# combined.net
KiCad netlist of a schematic drawn in EAGLE
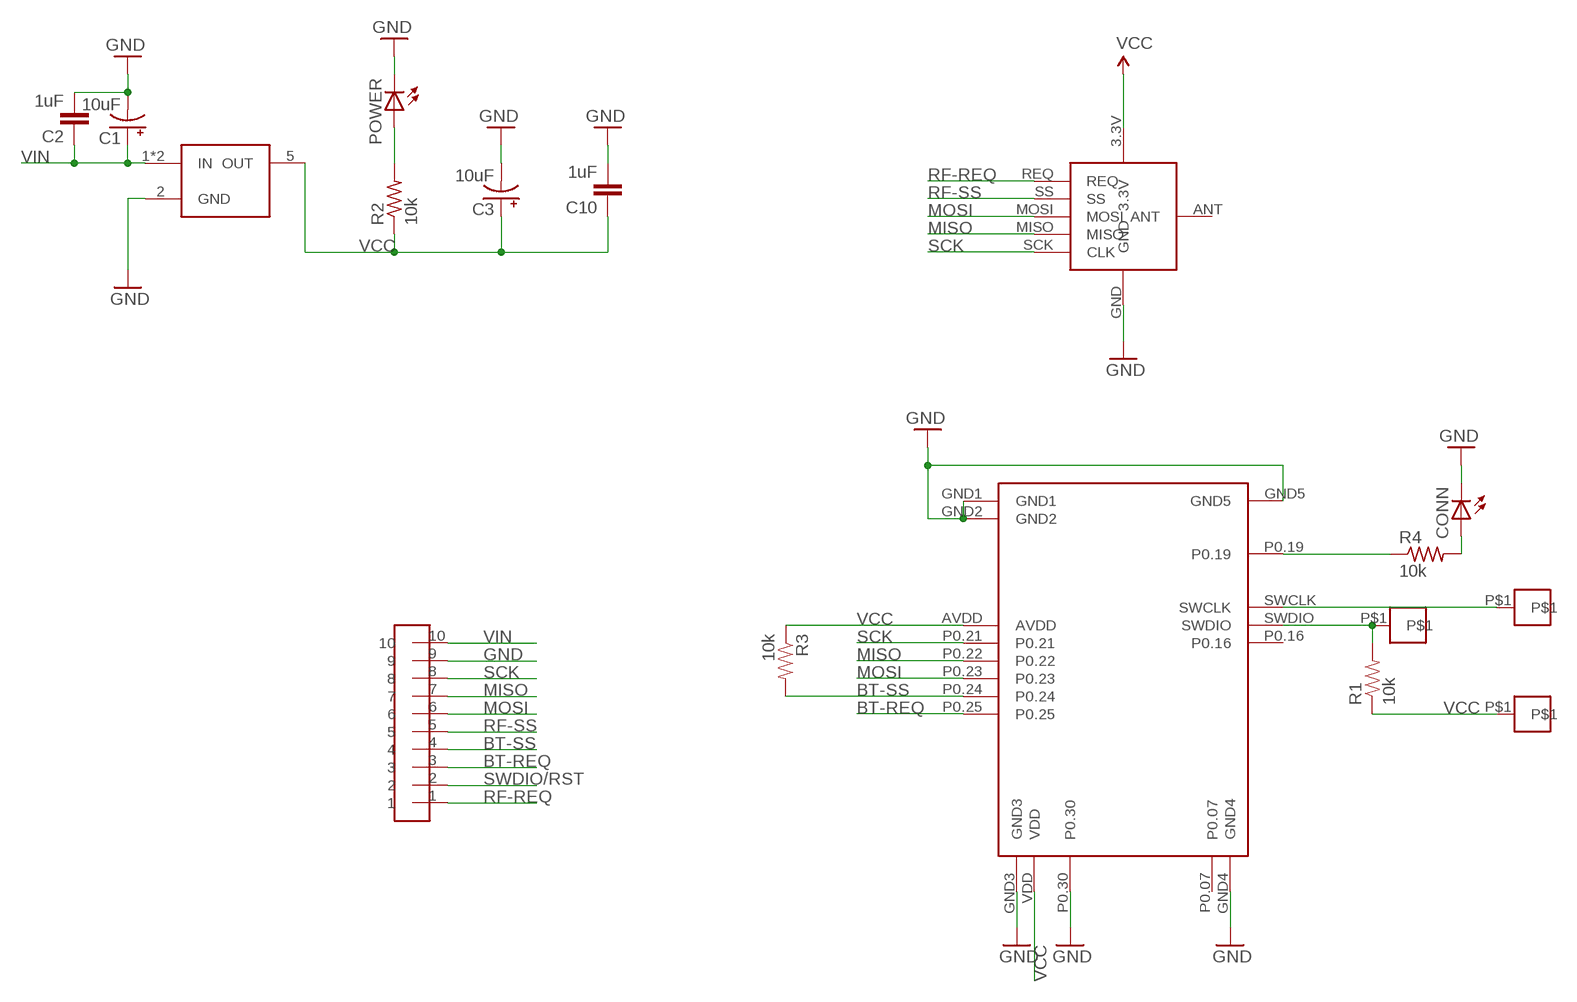
[diagram p0: schematic, sheet 1]

(export (version "E")
  (design (tool "Eeschema 10.0.6"))
  (components
    (comp (ref "C1")
      (value "10uF")
      (footprint "eagle-import:EIA3216")
      (libsource (lib "eagle-import") (part "CAP_POL1206"))
    )
    (comp (ref "C2")
      (value "1uF")
      (footprint "eagle-import:0603-CAP")
      (libsource (lib "eagle-import") (part "CAP0603-CAP"))
    )
    (comp (ref "C3")
      (value "10uF")
      (footprint "eagle-import:EIA3216")
      (libsource (lib "eagle-import") (part "CAP_POL1206"))
    )
    (comp (ref "C10")
      (value "1uF")
      (footprint "eagle-import:0603-CAP")
      (libsource (lib "eagle-import") (part "CAP0603-CAP"))
    )
    (comp (ref "CLOCK")
      (value "PAD")
      (footprint "eagle-import:SMD-ROUND")
      (libsource (lib "eagle-import") (part "PAD"))
    )
    (comp (ref "CLOCK1")
      (value "PAD")
      (footprint "eagle-import:SMD-ROUND")
      (libsource (lib "eagle-import") (part "PAD"))
    )
    (comp (ref "CONN")
      (value "LEDCHIP-LED0603")
      (footprint "eagle-import:CHIP-LED0603")
      (libsource (lib "eagle-import") (part "LEDCHIP-LED0603"))
    )
    (comp (ref "POWER")
      (value "LEDCHIP-LED0603")
      (footprint "eagle-import:CHIP-LED0603")
      (libsource (lib "eagle-import") (part "LEDCHIP-LED0603"))
    )
    (comp (ref "R1")
      (value "10k")
      (footprint "eagle-import:0603-RES")
      (libsource (lib "eagle-import") (part "RESISTOR0603"))
    )
    (comp (ref "R2")
      (value "10k")
      (footprint "eagle-import:R0603")
      (libsource (lib "eagle-import") (part "R-US_R0603"))
    )
    (comp (ref "R3")
      (value "10k")
      (footprint "eagle-import:0603-RES")
      (libsource (lib "eagle-import") (part "RESISTOR0603"))
    )
    (comp (ref "R4")
      (value "10k")
      (footprint "eagle-import:R0603")
      (libsource (lib "eagle-import") (part "R-US_R0603"))
    )
    (comp (ref "U$1")
      (value "RFM69")
      (footprint "eagle-import:S0C-RFM69")
      (libsource (lib "eagle-import") (part "RFM69"))
    )
    (comp (ref "U$2")
      (value "HEADER-10")
      (footprint "eagle-import:HEADER-10")
      (libsource (lib "eagle-import") (part "HEADER-10"))
    )
    (comp (ref "U$3")
      (value "REGULATOR3.3V-MIC5205")
      (footprint "eagle-import:SOT23-5")
      (libsource (lib "eagle-import") (part "REGULATOR3.3V-MIC5205"))
    )
    (comp (ref "U$5")
      (value "NRF51-MDBT40-SPI")
      (footprint "eagle-import:SOC-NRF51-MDBT40-SPI")
      (libsource (lib "eagle-import") (part "NRF51-MDBT40-SPI"))
    )
    (comp (ref "VCC")
      (value "PAD")
      (footprint "eagle-import:SMD-ROUND")
      (libsource (lib "eagle-import") (part "PAD"))
    )
  )
  (nets
    (net (code "1") (name "/BT-REQ") (class "Default")
      (node (ref "U$2") (pin "3") (pinfunction "3_3") (pintype "bidirectional"))
      (node (ref "U$5") (pin "P0.25") (pinfunction "P0.25_P0.25") (pintype "bidirectional"))
    )
    (net (code "2") (name "/BT-SS") (class "Default")
      (node (ref "R3") (pin "2") (pinfunction "2_2") (pintype "passive"))
      (node (ref "U$2") (pin "4") (pinfunction "4_4") (pintype "bidirectional"))
      (node (ref "U$5") (pin "P0.24") (pinfunction "P0.24_P0.24") (pintype "bidirectional"))
    )
    (net (code "3") (name "/MISO") (class "Default")
      (node (ref "U$1") (pin "MISO") (pinfunction "MISO_MISO") (pintype "bidirectional"))
      (node (ref "U$2") (pin "7") (pinfunction "7_7") (pintype "bidirectional"))
      (node (ref "U$5") (pin "P0.22") (pinfunction "P0.22_P0.22") (pintype "bidirectional"))
    )
    (net (code "4") (name "/MOSI") (class "Default")
      (node (ref "U$1") (pin "MOSI") (pinfunction "MOSI_MOSI") (pintype "bidirectional"))
      (node (ref "U$2") (pin "6") (pinfunction "6_6") (pintype "bidirectional"))
      (node (ref "U$5") (pin "P0.23") (pinfunction "P0.23_P0.23") (pintype "bidirectional"))
    )
    (net (code "5") (name "/RF-REQ") (class "Default")
      (node (ref "U$1") (pin "REQ") (pinfunction "REQ_REQ") (pintype "bidirectional"))
      (node (ref "U$2") (pin "1") (pinfunction "1_1") (pintype "bidirectional"))
    )
    (net (code "6") (name "/RF-SS") (class "Default")
      (node (ref "U$1") (pin "SS") (pinfunction "SS_SS") (pintype "bidirectional"))
      (node (ref "U$2") (pin "5") (pinfunction "5_5") (pintype "bidirectional"))
    )
    (net (code "7") (name "/SCK") (class "Default")
      (node (ref "U$1") (pin "SCK") (pinfunction "CLK_SCK") (pintype "bidirectional"))
      (node (ref "U$2") (pin "8") (pinfunction "8_8") (pintype "bidirectional"))
      (node (ref "U$5") (pin "P0.21") (pinfunction "P0.21_P0.21") (pintype "bidirectional"))
    )
    (net (code "8") (name "/SWDIO{slash}RST") (class "Default")
      (node (ref "CLOCK1") (pin "P$1") (pinfunction "P$1_P$1") (pintype "bidirectional"))
      (node (ref "R1") (pin "2") (pinfunction "2_2") (pintype "passive"))
      (node (ref "U$2") (pin "2") (pinfunction "2_2") (pintype "bidirectional"))
      (node (ref "U$5") (pin "SWDIO") (pinfunction "SWDIO_SWDIO") (pintype "bidirectional"))
    )
    (net (code "9") (name "/VIN") (class "Default")
      (node (ref "C1") (pin "A") (pinfunction "+_A") (pintype "passive"))
      (node (ref "C2") (pin "1") (pinfunction "1_1") (pintype "passive"))
      (node (ref "U$2") (pin "10") (pinfunction "10_10") (pintype "bidirectional"))
      (node (ref "U$3") (pin "1") (pinfunction "IN_1") (pintype "bidirectional"))
      (node (ref "U$3") (pin "3") (pinfunction "IN_3") (pintype "bidirectional"))
    )
    (net (code "10") (name "GND") (class "Default")
      (node (ref "C1") (pin "C") (pinfunction "-_C") (pintype "passive"))
      (node (ref "C10") (pin "2") (pinfunction "2_2") (pintype "passive"))
      (node (ref "C2") (pin "2") (pinfunction "2_2") (pintype "passive"))
      (node (ref "C3") (pin "C") (pinfunction "-_C") (pintype "passive"))
      (node (ref "CONN") (pin "C") (pinfunction "C_C") (pintype "passive"))
      (node (ref "POWER") (pin "C") (pinfunction "C_C") (pintype "passive"))
      (node (ref "U$1") (pin "GND") (pinfunction "GND_GND") (pintype "bidirectional"))
      (node (ref "U$2") (pin "9") (pinfunction "9_9") (pintype "bidirectional"))
      (node (ref "U$3") (pin "2") (pinfunction "GND_2") (pintype "bidirectional"))
      (node (ref "U$5") (pin "GND1") (pinfunction "GND1_GND1") (pintype "bidirectional"))
      (node (ref "U$5") (pin "GND2") (pinfunction "GND2_GND2") (pintype "bidirectional"))
      (node (ref "U$5") (pin "GND3") (pinfunction "GND3_GND3") (pintype "bidirectional"))
      (node (ref "U$5") (pin "GND4") (pinfunction "GND4_GND4") (pintype "bidirectional"))
      (node (ref "U$5") (pin "GND5") (pinfunction "GND5_GND5") (pintype "bidirectional"))
      (node (ref "U$5") (pin "P0.30") (pinfunction "P0.30_P0.30") (pintype "bidirectional"))
    )
    (net (code "11") (name "Net-(CLOCK-PadP$1)") (class "Default")
      (node (ref "CLOCK") (pin "P$1") (pinfunction "P$1_P$1") (pintype "bidirectional"))
      (node (ref "U$5") (pin "SWCLK") (pinfunction "SWCLK_SWCLK") (pintype "bidirectional"))
    )
    (net (code "12") (name "Net-(CONN-PadA)") (class "Default")
      (node (ref "CONN") (pin "A") (pinfunction "A_A") (pintype "passive"))
      (node (ref "R4") (pin "2") (pinfunction "2_2") (pintype "passive"))
    )
    (net (code "13") (name "Net-(POWER-PadA)") (class "Default")
      (node (ref "POWER") (pin "A") (pinfunction "A_A") (pintype "passive"))
      (node (ref "R2") (pin "2") (pinfunction "2_2") (pintype "passive"))
    )
    (net (code "14") (name "Net-(R4-Pad1)") (class "Default")
      (node (ref "R4") (pin "1") (pinfunction "1_1") (pintype "passive"))
      (node (ref "U$5") (pin "P0.19") (pinfunction "P0.19_P0.19") (pintype "bidirectional"))
    )
    (net (code "15") (name "VCC") (class "Default")
      (node (ref "C10") (pin "1") (pinfunction "1_1") (pintype "passive"))
      (node (ref "C3") (pin "A") (pinfunction "+_A") (pintype "passive"))
      (node (ref "R1") (pin "1") (pinfunction "1_1") (pintype "passive"))
      (node (ref "R2") (pin "1") (pinfunction "1_1") (pintype "passive"))
      (node (ref "R3") (pin "1") (pinfunction "1_1") (pintype "passive"))
      (node (ref "U$1") (pin "3.3V") (pinfunction "3.3V_3.3V") (pintype "bidirectional"))
      (node (ref "U$3") (pin "5") (pinfunction "OUT_5") (pintype "bidirectional"))
      (node (ref "U$5") (pin "AVDD") (pinfunction "AVDD_AVDD") (pintype "bidirectional"))
      (node (ref "U$5") (pin "VDD") (pinfunction "VDD_VDD") (pintype "bidirectional"))
      (node (ref "VCC") (pin "P$1") (pinfunction "P$1_P$1") (pintype "bidirectional"))
    )
    (net (code "16") (name "unconnected-(U$1-PadANT)") (class "Default")
      (node (ref "U$1") (pin "ANT") (pinfunction "ANT_ANT") (pintype "bidirectional"))
    )
    (net (code "17") (name "unconnected-(U$5-PadP0.07)") (class "Default")
      (node (ref "U$5") (pin "P0.07") (pinfunction "P0.07_P0.07") (pintype "bidirectional"))
    )
    (net (code "18") (name "unconnected-(U$5-PadP0.16)") (class "Default")
      (node (ref "U$5") (pin "P0.16") (pinfunction "P0.16_P0.16") (pintype "bidirectional"))
    )
  )
)
